# BAM_Reference_R2_0.net
KiCad netlist of a schematic drawn in EAGLE
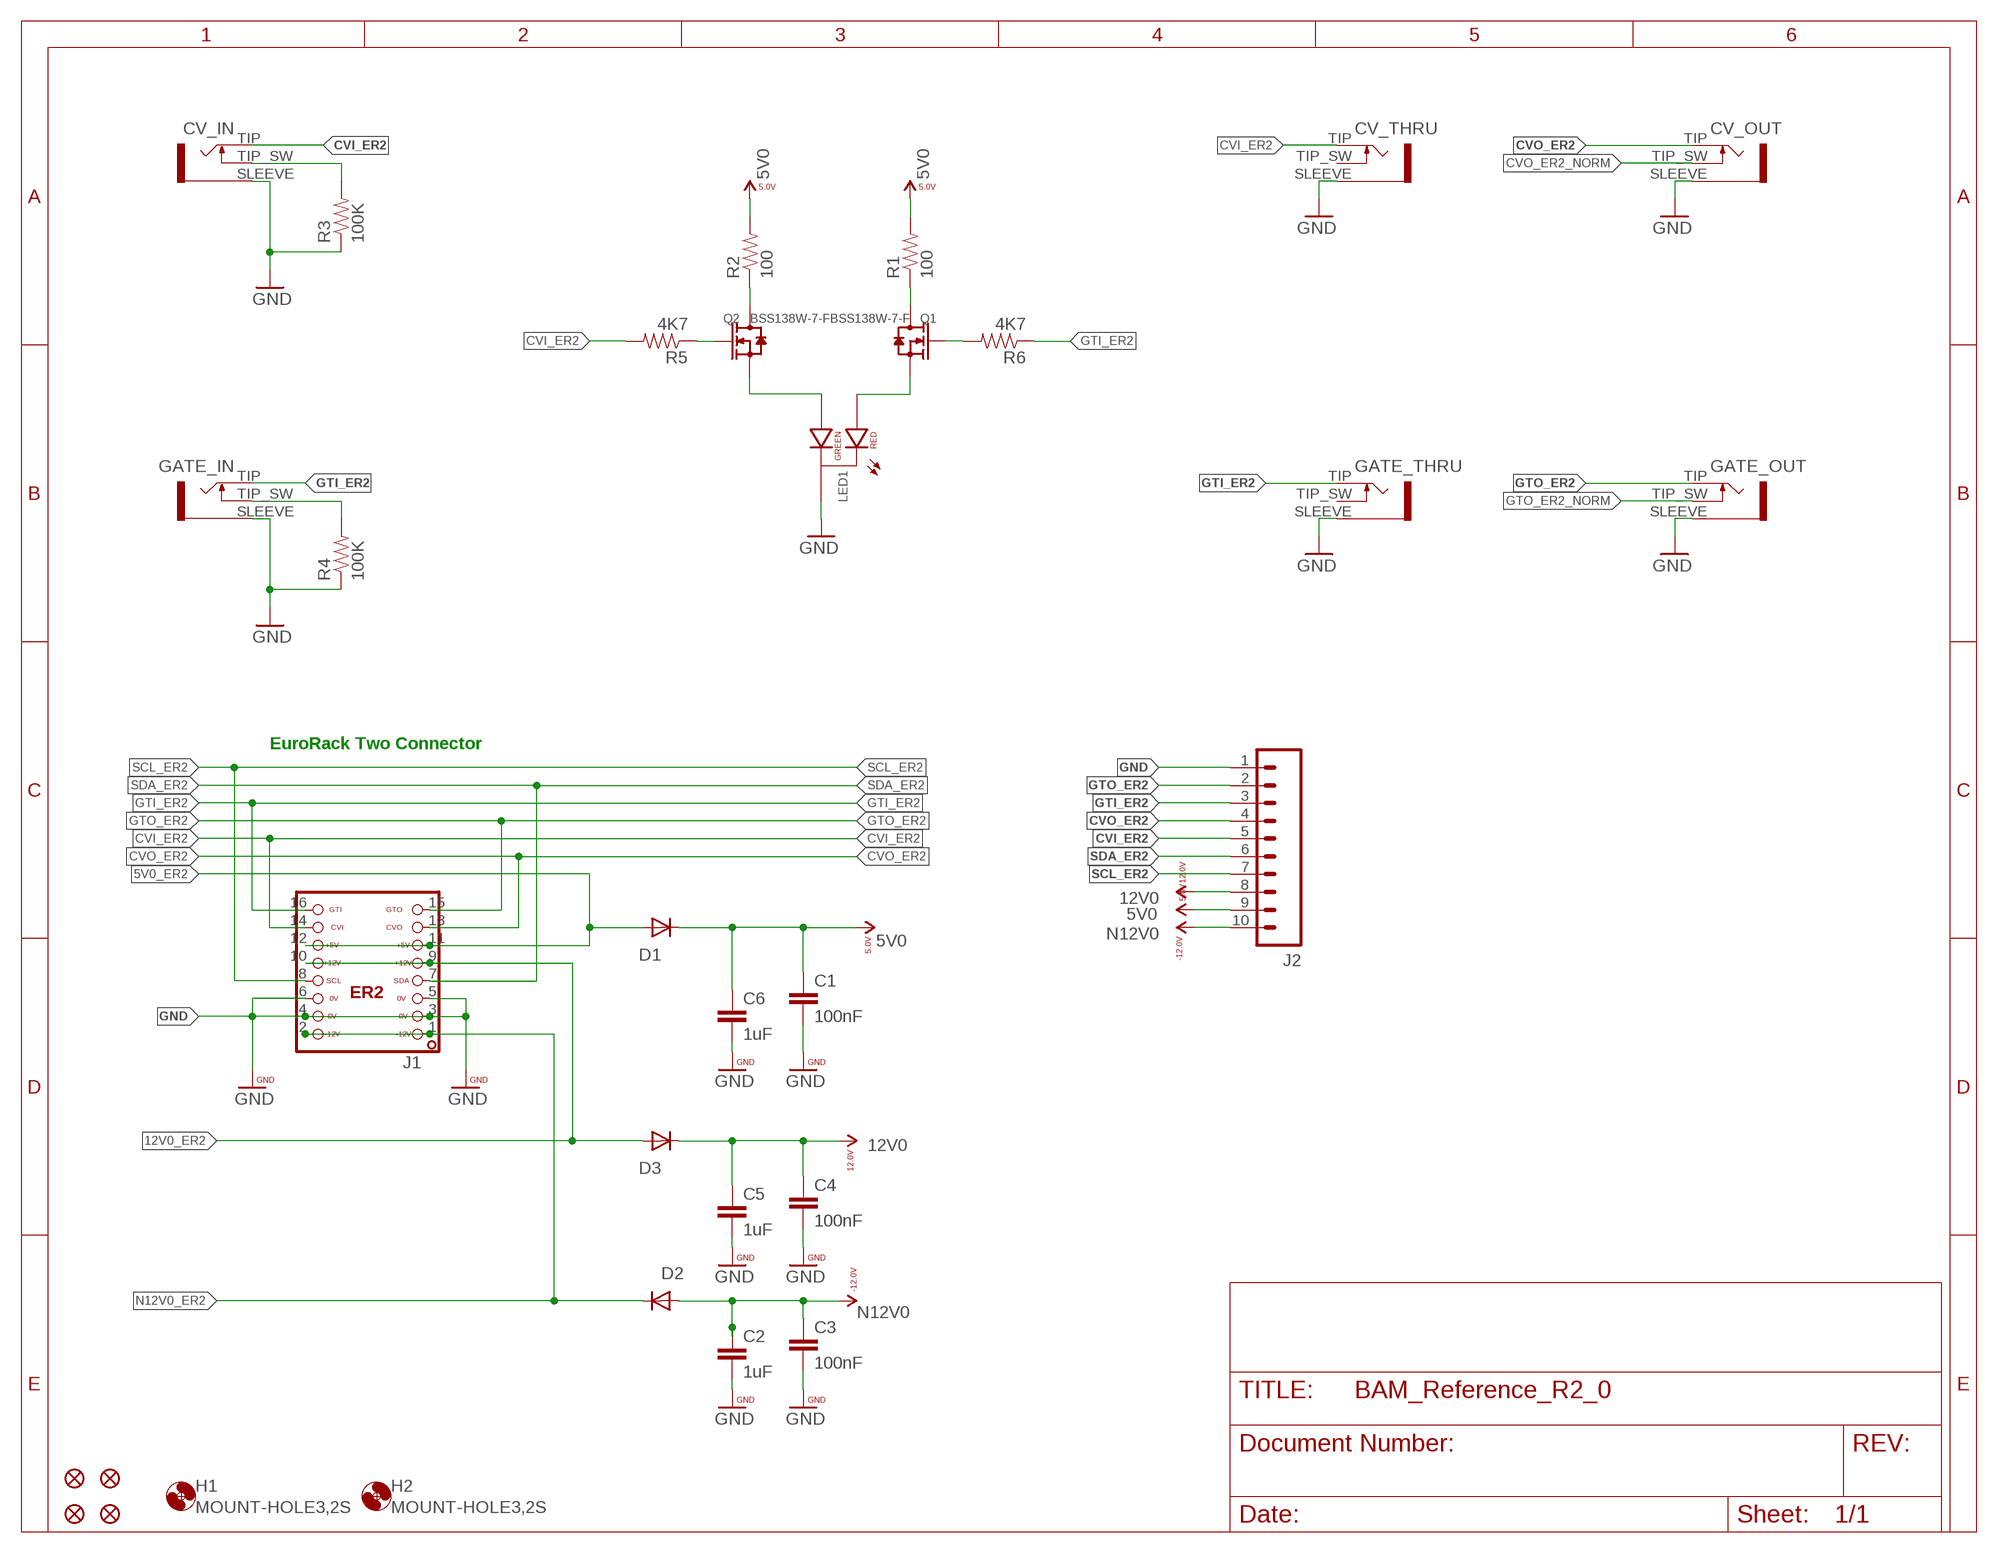
[diagram p0: schematic, sheet 1]

(export (version "E")
  (design (tool "Eeschema 10.0.6"))
  (components
    (comp (ref "C1")
      (value "100nF")
      (footprint "eagle-import:0603-CAP")
      (libsource (lib "eagle-import") (part "CAP0603-CAP"))
    )
    (comp (ref "C2")
      (value "1uF")
      (footprint "eagle-import:0603-CAP")
      (libsource (lib "eagle-import") (part "CAP0603-CAP"))
    )
    (comp (ref "C3")
      (value "100nF")
      (footprint "eagle-import:0603-CAP")
      (libsource (lib "eagle-import") (part "CAP0603-CAP"))
    )
    (comp (ref "C4")
      (value "100nF")
      (footprint "eagle-import:0603-CAP")
      (libsource (lib "eagle-import") (part "CAP0603-CAP"))
    )
    (comp (ref "C5")
      (value "1uF")
      (footprint "eagle-import:0603-CAP")
      (libsource (lib "eagle-import") (part "CAP0603-CAP"))
    )
    (comp (ref "C6")
      (value "1uF")
      (footprint "eagle-import:0603-CAP")
      (libsource (lib "eagle-import") (part "CAP0603-CAP"))
    )
    (comp (ref "CV_IN")
      (value "JACK-3_5MM-MONO-SW-MJ_3502")
      (footprint "eagle-import:MJ-3502")
      (libsource (lib "eagle-import") (part "oXo_Connectors_JACK-3_5MM-MONO-SW-MJ_3502"))
    )
    (comp (ref "CV_OUT")
      (value "JACK-3_5MM-MONO-SW-MJ_3502")
      (footprint "eagle-import:MJ-3502")
      (libsource (lib "eagle-import") (part "JACK-3_5MM-MONO-SW-MJ_3502"))
    )
    (comp (ref "CV_THRU")
      (value "JACK-3_5MM-MONO-SW-MJ_3502")
      (footprint "eagle-import:MJ-3502")
      (libsource (lib "eagle-import") (part "JACK-3_5MM-MONO-SW-MJ_3502"))
    )
    (comp (ref "D1")
      (value "1N5819HW")
      (footprint "eagle-import:SOD123")
      (libsource (lib "eagle-import") (part "DIODE-SOD123"))
    )
    (comp (ref "D2")
      (value "1N5819HW")
      (footprint "eagle-import:SOD123")
      (libsource (lib "eagle-import") (part "DIODE-SOD123"))
    )
    (comp (ref "D3")
      (value "1N5819HW")
      (footprint "eagle-import:SOD123")
      (libsource (lib "eagle-import") (part "DIODE-SOD123"))
    )
    (comp (ref "FID1")
      (value "FIDUCIALUFIDUCIAL")
      (footprint "eagle-import:MICRO-FIDUCIAL")
      (libsource (lib "eagle-import") (part "FIDUCIALUFIDUCIAL"))
    )
    (comp (ref "FID2")
      (value "FIDUCIALUFIDUCIAL")
      (footprint "eagle-import:MICRO-FIDUCIAL")
      (libsource (lib "eagle-import") (part "FIDUCIALUFIDUCIAL"))
    )
    (comp (ref "FID3")
      (value "FIDUCIALUFIDUCIAL")
      (footprint "eagle-import:MICRO-FIDUCIAL")
      (libsource (lib "eagle-import") (part "FIDUCIALUFIDUCIAL"))
    )
    (comp (ref "FID4")
      (value "FIDUCIALUFIDUCIAL")
      (footprint "eagle-import:MICRO-FIDUCIAL")
      (libsource (lib "eagle-import") (part "FIDUCIALUFIDUCIAL"))
    )
    (comp (ref "GATE_IN")
      (value "JACK-3_5MM-MONO-SW-MJ_3502")
      (footprint "eagle-import:MJ-3502")
      (libsource (lib "eagle-import") (part "oXo_Connectors_JACK-3_5MM-MONO-SW-MJ_3502"))
    )
    (comp (ref "GATE_OUT")
      (value "JACK-3_5MM-MONO-SW-MJ_3502")
      (footprint "eagle-import:MJ-3502")
      (libsource (lib "eagle-import") (part "JACK-3_5MM-MONO-SW-MJ_3502"))
    )
    (comp (ref "GATE_THRU")
      (value "JACK-3_5MM-MONO-SW-MJ_3502")
      (footprint "eagle-import:MJ-3502")
      (libsource (lib "eagle-import") (part "JACK-3_5MM-MONO-SW-MJ_3502"))
    )
    (comp (ref "H1")
      (value "MOUNT-HOLE3,2S")
      (footprint "eagle-import:3,2,SMALL")
      (libsource (lib "eagle-import") (part "MOUNT-HOLE3,2S"))
    )
    (comp (ref "H2")
      (value "MOUNT-HOLE3,2S")
      (footprint "eagle-import:3,2,SMALL")
      (libsource (lib "eagle-import") (part "MOUNT-HOLE3,2S"))
    )
    (comp (ref "J1")
      (value "ER2-SHROUD")
      (footprint "eagle-import:ER2")
      (libsource (lib "eagle-import") (part "ER2-SHROUD"))
    )
    (comp (ref "J2")
      (value "M10SILK_FEMALE_PTH")
      (footprint "eagle-import:1X10_OCTO")
      (libsource (lib "eagle-import") (part "M10SILK_FEMALE_PTH"))
    )
    (comp (ref "LED1")
      (value "LED-RG-CC-PTH-G18500")
      (footprint "eagle-import:LED-RG-PANEL")
      (libsource (lib "eagle-import") (part "LED-RG-CC-PTH-G18500"))
    )
    (comp (ref "Q1")
      (value "BSS138W-7-F")
      (footprint "eagle-import:SOT-23")
      (libsource (lib "eagle-import") (part "SMD-MOSFET-N-CH-50V-200MA-BSS138W-7-F(SOT-23)"))
    )
    (comp (ref "Q2")
      (value "BSS138W-7-F")
      (footprint "eagle-import:SOT-23")
      (libsource (lib "eagle-import") (part "SMD-MOSFET-N-CH-50V-200MA-BSS138W-7-F(SOT-23)"))
    )
    (comp (ref "R1")
      (value "100")
      (footprint "eagle-import:0603-RES")
      (libsource (lib "eagle-import") (part "RESISTOR0603"))
    )
    (comp (ref "R2")
      (value "100")
      (footprint "eagle-import:0603-RES")
      (libsource (lib "eagle-import") (part "RESISTOR0603"))
    )
    (comp (ref "R3")
      (value "100K")
      (footprint "eagle-import:0603-RES")
      (libsource (lib "eagle-import") (part "RESISTOR0603"))
    )
    (comp (ref "R4")
      (value "100K")
      (footprint "eagle-import:0603-RES")
      (libsource (lib "eagle-import") (part "RESISTOR0603"))
    )
    (comp (ref "R5")
      (value "4K7")
      (footprint "eagle-import:0603-RES")
      (libsource (lib "eagle-import") (part "RESISTOR0603"))
    )
    (comp (ref "R6")
      (value "4K7")
      (footprint "eagle-import:0603-RES")
      (libsource (lib "eagle-import") (part "RESISTOR0603"))
    )
  )
  (nets
    (net (code "1") (name "5V0") (class "Default")
      (node (ref "C1") (pin "1") (pinfunction "1_1") (pintype "passive"))
      (node (ref "C6") (pin "1") (pinfunction "1_1") (pintype "passive"))
      (node (ref "D1") (pin "C") (pinfunction "C_C") (pintype "passive"))
      (node (ref "J2") (pin "9") (pinfunction "9_9") (pintype "passive"))
      (node (ref "R1") (pin "2") (pinfunction "2_2") (pintype "passive"))
      (node (ref "R2") (pin "2") (pinfunction "2_2") (pintype "passive"))
    )
    (net (code "2") (name "5V0_ER2") (class "Default")
      (node (ref "D1") (pin "A") (pinfunction "A_A") (pintype "passive"))
      (node (ref "J1") (pin "11") (pinfunction "11_11") (pintype "passive"))
      (node (ref "J1") (pin "12") (pinfunction "12_12") (pintype "passive"))
    )
    (net (code "3") (name "12V0") (class "Default")
      (node (ref "C4") (pin "1") (pinfunction "1_1") (pintype "passive"))
      (node (ref "C5") (pin "1") (pinfunction "1_1") (pintype "passive"))
      (node (ref "D3") (pin "C") (pinfunction "C_C") (pintype "passive"))
      (node (ref "J2") (pin "8") (pinfunction "8_8") (pintype "passive"))
    )
    (net (code "4") (name "12V0_ER2") (class "Default")
      (node (ref "D3") (pin "A") (pinfunction "A_A") (pintype "passive"))
      (node (ref "J1") (pin "10") (pinfunction "10_10") (pintype "passive"))
      (node (ref "J1") (pin "9") (pinfunction "9_9") (pintype "passive"))
    )
    (net (code "5") (name "CVI_ER2") (class "Default")
      (node (ref "CV_IN") (pin "TIP") (pinfunction "TIP_TIP") (pintype "passive"))
      (node (ref "CV_THRU") (pin "TIP") (pinfunction "TIP_TIP") (pintype "passive"))
      (node (ref "J1") (pin "14") (pinfunction "14_14") (pintype "passive"))
      (node (ref "J2") (pin "5") (pinfunction "5_5") (pintype "passive"))
      (node (ref "R5") (pin "2") (pinfunction "2_2") (pintype "passive"))
    )
    (net (code "6") (name "CVO_ER2") (class "Default")
      (node (ref "CV_OUT") (pin "TIP") (pinfunction "TIP_TIP") (pintype "passive"))
      (node (ref "J1") (pin "13") (pinfunction "13_13") (pintype "passive"))
      (node (ref "J2") (pin "4") (pinfunction "4_4") (pintype "passive"))
    )
    (net (code "7") (name "CVO_ER2_NORM") (class "Default")
      (node (ref "CV_OUT") (pin "TIP_SW") (pinfunction "TIP_SW_TIP_SW") (pintype "passive"))
    )
    (net (code "8") (name "GND") (class "Default")
      (node (ref "C1") (pin "2") (pinfunction "2_2") (pintype "passive"))
      (node (ref "C2") (pin "2") (pinfunction "2_2") (pintype "passive"))
      (node (ref "C3") (pin "2") (pinfunction "2_2") (pintype "passive"))
      (node (ref "C4") (pin "2") (pinfunction "2_2") (pintype "passive"))
      (node (ref "C5") (pin "2") (pinfunction "2_2") (pintype "passive"))
      (node (ref "C6") (pin "2") (pinfunction "2_2") (pintype "passive"))
      (node (ref "CV_IN") (pin "SLEEVE") (pinfunction "SLEEVE_SLEEVE") (pintype "passive"))
      (node (ref "CV_OUT") (pin "SLEEVE") (pinfunction "SLEEVE_SLEEVE") (pintype "passive"))
      (node (ref "CV_THRU") (pin "SLEEVE") (pinfunction "SLEEVE_SLEEVE") (pintype "passive"))
      (node (ref "GATE_IN") (pin "SLEEVE") (pinfunction "SLEEVE_SLEEVE") (pintype "passive"))
      (node (ref "GATE_OUT") (pin "SLEEVE") (pinfunction "SLEEVE_SLEEVE") (pintype "passive"))
      (node (ref "GATE_THRU") (pin "SLEEVE") (pinfunction "SLEEVE_SLEEVE") (pintype "passive"))
      (node (ref "J1") (pin "3") (pinfunction "3_3") (pintype "passive"))
      (node (ref "J1") (pin "4") (pinfunction "4_4") (pintype "passive"))
      (node (ref "J1") (pin "5") (pinfunction "5_5") (pintype "passive"))
      (node (ref "J1") (pin "6") (pinfunction "6_6") (pintype "passive"))
      (node (ref "J2") (pin "1") (pinfunction "1_1") (pintype "passive"))
      (node (ref "LED1") (pin "CC") (pinfunction "CATHODE_CC") (pintype "bidirectional"))
      (node (ref "R3") (pin "1") (pinfunction "1_1") (pintype "passive"))
      (node (ref "R4") (pin "1") (pinfunction "1_1") (pintype "passive"))
    )
    (net (code "9") (name "GTI_ER2") (class "Default")
      (node (ref "GATE_IN") (pin "TIP") (pinfunction "TIP_TIP") (pintype "passive"))
      (node (ref "GATE_THRU") (pin "TIP") (pinfunction "TIP_TIP") (pintype "passive"))
      (node (ref "J1") (pin "16") (pinfunction "16_16") (pintype "passive"))
      (node (ref "J2") (pin "3") (pinfunction "3_3") (pintype "passive"))
      (node (ref "R6") (pin "1") (pinfunction "1_1") (pintype "passive"))
    )
    (net (code "10") (name "GTO_ER2") (class "Default")
      (node (ref "GATE_OUT") (pin "TIP") (pinfunction "TIP_TIP") (pintype "passive"))
      (node (ref "J1") (pin "15") (pinfunction "15_15") (pintype "passive"))
      (node (ref "J2") (pin "2") (pinfunction "2_2") (pintype "passive"))
    )
    (net (code "11") (name "GTO_ER2_NORM") (class "Default")
      (node (ref "GATE_OUT") (pin "TIP_SW") (pinfunction "TIP_SW_TIP_SW") (pintype "passive"))
    )
    (net (code "12") (name "N12V0") (class "Default")
      (node (ref "C2") (pin "1") (pinfunction "1_1") (pintype "passive"))
      (node (ref "C3") (pin "1") (pinfunction "1_1") (pintype "passive"))
      (node (ref "D2") (pin "A") (pinfunction "A_A") (pintype "passive"))
      (node (ref "J2") (pin "10") (pinfunction "10_10") (pintype "passive"))
    )
    (net (code "13") (name "N12V0_ER2") (class "Default")
      (node (ref "D2") (pin "C") (pinfunction "C_C") (pintype "passive"))
      (node (ref "J1") (pin "1") (pinfunction "1_1") (pintype "passive"))
      (node (ref "J1") (pin "2") (pinfunction "2_2") (pintype "passive"))
    )
    (net (code "14") (name "Net-(CV_IN-PadTIP_SW)") (class "Default")
      (node (ref "CV_IN") (pin "TIP_SW") (pinfunction "TIP_SW_TIP_SW") (pintype "passive"))
      (node (ref "R3") (pin "2") (pinfunction "2_2") (pintype "passive"))
    )
    (net (code "15") (name "Net-(GATE_IN-PadTIP_SW)") (class "Default")
      (node (ref "GATE_IN") (pin "TIP_SW") (pinfunction "TIP_SW_TIP_SW") (pintype "passive"))
      (node (ref "R4") (pin "2") (pinfunction "2_2") (pintype "passive"))
    )
    (net (code "16") (name "Net-(LED1-GREEN_CATHODE)") (class "Default")
      (node (ref "LED1") (pin "GREEN") (pinfunction "GREEN_CATHODE_GREEN") (pintype "bidirectional"))
      (node (ref "Q2") (pin "2") (pinfunction "S_2") (pintype "passive"))
    )
    (net (code "17") (name "Net-(LED1-RED_CATHODE)") (class "Default")
      (node (ref "LED1") (pin "RED") (pinfunction "RED_CATHODE_RED") (pintype "bidirectional"))
      (node (ref "Q1") (pin "2") (pinfunction "S_2") (pintype "passive"))
    )
    (net (code "18") (name "Net-(Q1-D)") (class "Default")
      (node (ref "Q1") (pin "3") (pinfunction "D_3") (pintype "passive"))
      (node (ref "R1") (pin "1") (pinfunction "1_1") (pintype "passive"))
    )
    (net (code "19") (name "Net-(Q1-G)") (class "Default")
      (node (ref "Q1") (pin "1") (pinfunction "G_1") (pintype "passive"))
      (node (ref "R6") (pin "2") (pinfunction "2_2") (pintype "passive"))
    )
    (net (code "20") (name "Net-(Q2-D)") (class "Default")
      (node (ref "Q2") (pin "3") (pinfunction "D_3") (pintype "passive"))
      (node (ref "R2") (pin "1") (pinfunction "1_1") (pintype "passive"))
    )
    (net (code "21") (name "Net-(Q2-G)") (class "Default")
      (node (ref "Q2") (pin "1") (pinfunction "G_1") (pintype "passive"))
      (node (ref "R5") (pin "1") (pinfunction "1_1") (pintype "passive"))
    )
    (net (code "22") (name "SCL_ER2") (class "Default")
      (node (ref "J1") (pin "8") (pinfunction "8_8") (pintype "passive"))
      (node (ref "J2") (pin "7") (pinfunction "7_7") (pintype "passive"))
    )
    (net (code "23") (name "SDA_ER2") (class "Default")
      (node (ref "J1") (pin "7") (pinfunction "7_7") (pintype "passive"))
      (node (ref "J2") (pin "6") (pinfunction "6_6") (pintype "passive"))
    )
    (net (code "24") (name "unconnected-(CV_THRU-PadTIP_SW)") (class "Default")
      (node (ref "CV_THRU") (pin "TIP_SW") (pinfunction "TIP_SW_TIP_SW") (pintype "passive"))
    )
    (net (code "25") (name "unconnected-(GATE_THRU-PadTIP_SW)") (class "Default")
      (node (ref "GATE_THRU") (pin "TIP_SW") (pinfunction "TIP_SW_TIP_SW") (pintype "passive"))
    )
  )
)
